# FC.net
KiCad netlist of a schematic drawn in Altium Designer
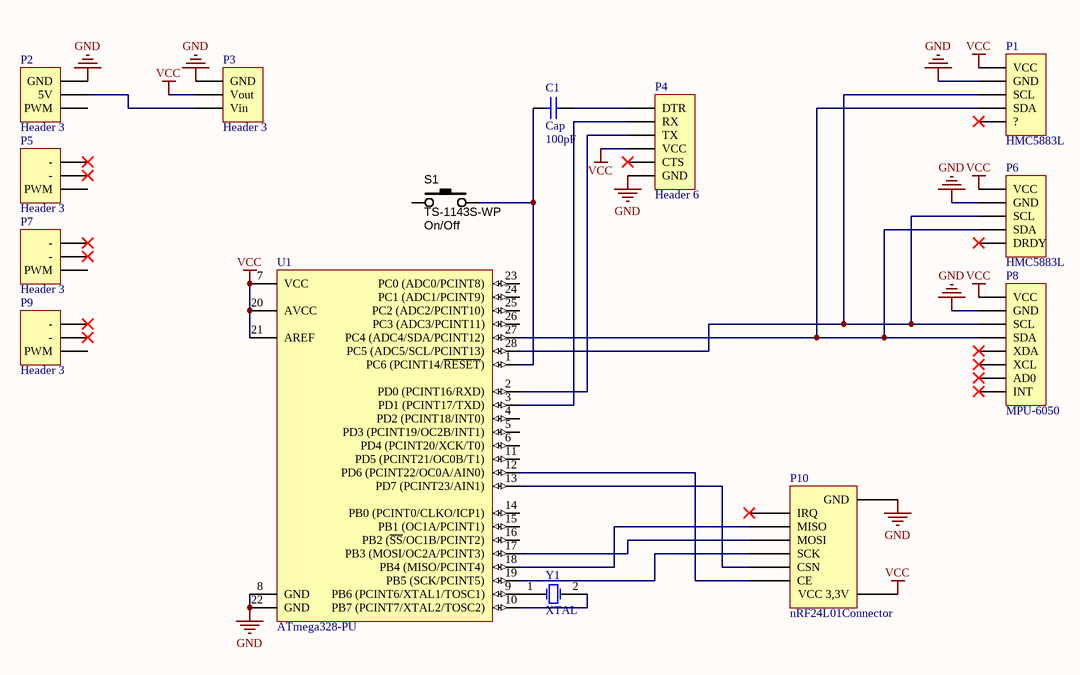
[diagram p0: FC.SchDoc]

(export (version "E")
  (design (tool "Eeschema 10.0.6"))
  (components
    (comp (ref "C1")
      (value "Cap")
      (footprint "RAD-0.3")
      (description "Capacitor")
      (fields (field (name "ALTIUM_VALUE") "100pF") (field (name "PUBLISHER") "Altium Limited"))
      (libsource (lib "Miscellaneous Devices") (part "Cap"))
    )
    (comp (ref "P1")
      (value "HMC5883L")
      (footprint "HDR1X5")
      (description "Header, 5-Pin")
      (fields (field (name "PUBLISHER") "Altium Limited"))
      (libsource (lib "Miscellaneous Connectors") (part "Header 5"))
    )
    (comp (ref "P2")
      (value "Header 3")
      (footprint "HDR1X3")
      (description "Header, 3-Pin")
      (fields (field (name "PUBLISHER") "Altium Limited"))
      (libsource (lib "Miscellaneous Connectors") (part "Header 3"))
    )
    (comp (ref "P3")
      (value "Header 3")
      (footprint "HDR1X3")
      (description "Header, 3-Pin")
      (fields (field (name "PUBLISHER") "Altium Limited"))
      (libsource (lib "") (part "Header 3_1"))
    )
    (comp (ref "P4")
      (value "Header 6")
      (footprint "HDR1X6")
      (description "Header, 6-Pin")
      (fields (field (name "PUBLISHER") "Altium Limited"))
      (libsource (lib "Miscellaneous Connectors") (part "Header 6"))
    )
    (comp (ref "P5")
      (value "Header 3")
      (footprint "HDR1X3")
      (description "Header, 3-Pin")
      (fields (field (name "PUBLISHER") "Altium Limited"))
      (libsource (lib "Miscellaneous Connectors") (part "Header 3"))
    )
    (comp (ref "P6")
      (value "HMC5883L")
      (footprint "HDR1X5")
      (description "Header, 5-Pin")
      (fields (field (name "PUBLISHER") "Altium Limited"))
      (libsource (lib "Miscellaneous Connectors") (part "Header 5"))
    )
    (comp (ref "P7")
      (value "Header 3")
      (footprint "HDR1X3")
      (description "Header, 3-Pin")
      (fields (field (name "PUBLISHER") "Altium Limited"))
      (libsource (lib "Miscellaneous Connectors") (part "Header 3"))
    )
    (comp (ref "P8")
      (value "MPU-6050")
      (footprint "HDR1X8")
      (description "Header, 8-Pin")
      (fields (field (name "PUBLISHER") "Altium Limited"))
      (libsource (lib "Miscellaneous Connectors") (part "Header 8"))
    )
    (comp (ref "P9")
      (value "Header 3")
      (footprint "HDR1X3")
      (description "Header, 3-Pin")
      (fields (field (name "PUBLISHER") "Altium Limited"))
      (libsource (lib "Miscellaneous Connectors") (part "Header 3"))
    )
    (comp (ref "P10")
      (value "nRF24L01Connector")
      (footprint "HDR2X4")
      (libsource (lib "nRF24L01Connector") (part "nRF24L01Connector"))
    )
    (comp (ref "S1")
      (value "TS-1143S-WP")
      (footprint "TS-1143S")
      (description "Switch SMD Tact 4.3mm Stem")
      (fields (field (name "FUNCTION") "On/Off"))
      (libsource (lib "PBL - Switches") (part "SW_SMD_PB_4.3mm"))
    )
    (comp (ref "U1")
      (value "ATmega328-PU")
      (footprint "28P3")
      (fields (field (name "PUBLISHER") "Altium Limited"))
      (libsource (lib "Atmel Microcontroller 8-Bit megaAVR") (part "ATmega328-PU"))
    )
    (comp (ref "Y1")
      (value "XTAL")
      (footprint "R38")
      (description "Crystal Oscillator")
      (fields (field (name "PUBLISHER") "Altium Limited"))
      (libsource (lib "Miscellaneous Devices") (part "XTAL"))
    )
  )
  (nets
    (net (code "1") (name "GND") (class "Default")
      (node (ref "P1") (pin "2") (pinfunction "GND_2") (pintype "passive"))
      (node (ref "P10") (pin "2") (pinfunction "GND_2") (pintype "passive"))
      (node (ref "P2") (pin "3") (pinfunction "-_3") (pintype "passive"))
      (node (ref "P3") (pin "1") (pinfunction "GND_1") (pintype "passive"))
      (node (ref "P4") (pin "6") (pinfunction "GND_6") (pintype "passive"))
      (node (ref "P6") (pin "2") (pinfunction "GND_2") (pintype "passive"))
      (node (ref "P8") (pin "2") (pinfunction "GND_2") (pintype "passive"))
      (node (ref "U1") (pin "22") (pinfunction "GND_22") (pintype "power_in"))
      (node (ref "U1") (pin "8") (pinfunction "GND_8") (pintype "power_in"))
    )
    (net (code "2") (name "Net-(P1-SCL)") (class "Default")
      (node (ref "P1") (pin "3") (pinfunction "SCL_3") (pintype "passive"))
      (node (ref "P6") (pin "3") (pinfunction "SCL_3") (pintype "passive"))
      (node (ref "P8") (pin "3") (pinfunction "SCL_3") (pintype "passive"))
      (node (ref "U1") (pin "28") (pinfunction "PC5_(ADC5/SCL/PCINT13)_28") (pintype "bidirectional"))
    )
    (net (code "3") (name "Net-(P1-SDA)") (class "Default")
      (node (ref "P1") (pin "4") (pinfunction "SDA_4") (pintype "passive"))
      (node (ref "P6") (pin "4") (pinfunction "SDA_4") (pintype "passive"))
      (node (ref "P8") (pin "4") (pinfunction "SDA_4") (pintype "passive"))
      (node (ref "U1") (pin "27") (pinfunction "PC4_(ADC4/SDA/PCINT12)_27") (pintype "bidirectional"))
    )
    (net (code "4") (name "Net-(P3-Vin)") (class "Default")
      (node (ref "P2") (pin "2") (pinfunction "-_2") (pintype "passive"))
      (node (ref "P3") (pin "3") (pinfunction "Vin_3") (pintype "passive"))
    )
    (net (code "5") (name "Net-(P4-DTR)") (class "Default")
      (node (ref "C1") (pin "2") (pinfunction "2_2") (pintype "passive"))
      (node (ref "P4") (pin "1") (pinfunction "DTR_1") (pintype "passive"))
    )
    (net (code "6") (name "Net-(P4-RX)") (class "Default")
      (node (ref "P4") (pin "2") (pinfunction "RX_2") (pintype "passive"))
      (node (ref "U1") (pin "3") (pinfunction "PD1_(PCINT17/TXD)_3") (pintype "bidirectional"))
    )
    (net (code "7") (name "Net-(P4-TX)") (class "Default")
      (node (ref "P4") (pin "3") (pinfunction "TX_3") (pintype "passive"))
      (node (ref "U1") (pin "2") (pinfunction "PD0_(PCINT16/RXD)_2") (pintype "bidirectional"))
    )
    (net (code "8") (name "Net-(P10-CE)") (class "Default")
      (node (ref "P10") (pin "3") (pinfunction "CE_3") (pintype "passive"))
      (node (ref "U1") (pin "12") (pinfunction "PD6_(PCINT22/OC0A/AIN0)_12") (pintype "bidirectional"))
    )
    (net (code "9") (name "Net-(P10-CSN)") (class "Default")
      (node (ref "P10") (pin "4") (pinfunction "CSN_4") (pintype "passive"))
      (node (ref "U1") (pin "13") (pinfunction "PD7_(PCINT23/AIN1)_13") (pintype "bidirectional"))
    )
    (net (code "10") (name "Net-(P10-MISO)") (class "Default")
      (node (ref "P10") (pin "7") (pinfunction "MISO_7") (pintype "passive"))
      (node (ref "U1") (pin "18") (pinfunction "PB4_(MISO/PCINT4)_18") (pintype "bidirectional"))
    )
    (net (code "11") (name "Net-(P10-MOSI)") (class "Default")
      (node (ref "P10") (pin "6") (pinfunction "MOSI_6") (pintype "passive"))
      (node (ref "U1") (pin "17") (pinfunction "PB3_(MOSI/OC2A/PCINT3)_17") (pintype "bidirectional"))
    )
    (net (code "12") (name "Net-(P10-SCK)") (class "Default")
      (node (ref "P10") (pin "5") (pinfunction "SCK_5") (pintype "passive"))
      (node (ref "U1") (pin "19") (pinfunction "PB5_(SCK/PCINT5)_19") (pintype "bidirectional"))
    )
    (net (code "13") (name "Net-(U1-PB6_(PCINT6{slash}XTAL1{slash}TOSC1))") (class "Default")
      (node (ref "U1") (pin "9") (pinfunction "PB6_(PCINT6/XTAL1/TOSC1)_9") (pintype "bidirectional"))
      (node (ref "Y1") (pin "1") (pinfunction "OSC1_1") (pintype "passive"))
    )
    (net (code "14") (name "Net-(U1-PB7_(PCINT7{slash}XTAL2{slash}TOSC2))") (class "Default")
      (node (ref "U1") (pin "10") (pinfunction "PB7_(PCINT7/XTAL2/TOSC2)_10") (pintype "bidirectional"))
      (node (ref "Y1") (pin "2") (pinfunction "OSC2_2") (pintype "passive"))
    )
    (net (code "15") (name "Net-(U1-PC6_(PCINT14{slash}~{RESET}))") (class "Default")
      (node (ref "C1") (pin "1") (pinfunction "1_1") (pintype "passive"))
      (node (ref "S1") (pin "2") (pintype "passive"))
      (node (ref "U1") (pin "1") (pinfunction "PC6_(PCINT14/~{RESET})_1") (pintype "bidirectional"))
    )
    (net (code "16") (name "VCC") (class "Default")
      (node (ref "P1") (pin "1") (pinfunction "VCC_1") (pintype "passive"))
      (node (ref "P10") (pin "1") (pinfunction "VCC_3,3V_1") (pintype "passive"))
      (node (ref "P3") (pin "2") (pinfunction "Vout_2") (pintype "passive"))
      (node (ref "P4") (pin "4") (pinfunction "VCC_4") (pintype "passive"))
      (node (ref "P6") (pin "1") (pinfunction "VCC_1") (pintype "passive"))
      (node (ref "P8") (pin "1") (pinfunction "VCC_1") (pintype "passive"))
      (node (ref "U1") (pin "20") (pinfunction "AVCC_20") (pintype "power_in"))
      (node (ref "U1") (pin "21") (pinfunction "AREF_21") (pintype "power_in"))
      (node (ref "U1") (pin "7") (pinfunction "VCC_7") (pintype "power_in"))
    )
    (net (code "17") (name "unconnected-(P1-DRDY-Pad5)") (class "Default")
      (node (ref "P1") (pin "5") (pinfunction "DRDY_5") (pintype "passive+no_connect"))
    )
    (net (code "18") (name "unconnected-(P2-PWM-Pad1)") (class "Default")
      (node (ref "P2") (pin "1") (pinfunction "PWM_1") (pintype "passive"))
    )
    (net (code "19") (name "unconnected-(P4-CTS-Pad5)") (class "Default")
      (node (ref "P4") (pin "5") (pinfunction "CTS_5") (pintype "passive+no_connect"))
    )
    (net (code "20") (name "unconnected-(P5---Pad2)") (class "Default")
      (node (ref "P5") (pin "2") (pinfunction "-_2") (pintype "passive+no_connect"))
    )
    (net (code "21") (name "unconnected-(P5---Pad3)") (class "Default")
      (node (ref "P5") (pin "3") (pinfunction "-_3") (pintype "passive+no_connect"))
    )
    (net (code "22") (name "unconnected-(P5-PWM-Pad1)") (class "Default")
      (node (ref "P5") (pin "1") (pinfunction "PWM_1") (pintype "passive"))
    )
    (net (code "23") (name "unconnected-(P6-DRDY-Pad5)") (class "Default")
      (node (ref "P6") (pin "5") (pinfunction "DRDY_5") (pintype "passive+no_connect"))
    )
    (net (code "24") (name "unconnected-(P7---Pad2)") (class "Default")
      (node (ref "P7") (pin "2") (pinfunction "-_2") (pintype "passive+no_connect"))
    )
    (net (code "25") (name "unconnected-(P7---Pad3)") (class "Default")
      (node (ref "P7") (pin "3") (pinfunction "-_3") (pintype "passive+no_connect"))
    )
    (net (code "26") (name "unconnected-(P7-PWM-Pad1)") (class "Default")
      (node (ref "P7") (pin "1") (pinfunction "PWM_1") (pintype "passive"))
    )
    (net (code "27") (name "unconnected-(P8-AD0-Pad7)") (class "Default")
      (node (ref "P8") (pin "7") (pinfunction "AD0_7") (pintype "passive+no_connect"))
    )
    (net (code "28") (name "unconnected-(P8-INT-Pad8)") (class "Default")
      (node (ref "P8") (pin "8") (pinfunction "INT_8") (pintype "passive+no_connect"))
    )
    (net (code "29") (name "unconnected-(P8-XCL-Pad6)") (class "Default")
      (node (ref "P8") (pin "6") (pinfunction "XCL_6") (pintype "passive+no_connect"))
    )
    (net (code "30") (name "unconnected-(P8-XDA-Pad5)") (class "Default")
      (node (ref "P8") (pin "5") (pinfunction "XDA_5") (pintype "passive+no_connect"))
    )
    (net (code "31") (name "unconnected-(P9---Pad2)") (class "Default")
      (node (ref "P9") (pin "2") (pinfunction "-_2") (pintype "passive+no_connect"))
    )
    (net (code "32") (name "unconnected-(P9---Pad3)") (class "Default")
      (node (ref "P9") (pin "3") (pinfunction "-_3") (pintype "passive+no_connect"))
    )
    (net (code "33") (name "unconnected-(P9-PWM-Pad1)") (class "Default")
      (node (ref "P9") (pin "1") (pinfunction "PWM_1") (pintype "passive"))
    )
    (net (code "34") (name "unconnected-(P10-IRQ-Pad8)") (class "Default")
      (node (ref "P10") (pin "8") (pinfunction "IRQ_8") (pintype "passive+no_connect"))
    )
    (net (code "35") (name "unconnected-(S1-Pad1)") (class "Default")
      (node (ref "S1") (pin "1") (pintype "passive"))
    )
    (net (code "36") (name "unconnected-(U1-PB0_(PCINT0{slash}CLKO{slash}ICP1)-Pad14)") (class "Default")
      (node (ref "U1") (pin "14") (pinfunction "PB0_(PCINT0/CLKO/ICP1)_14") (pintype "bidirectional"))
    )
    (net (code "37") (name "unconnected-(U1-PB1_(OC1A{slash}PCINT1)-Pad15)") (class "Default")
      (node (ref "U1") (pin "15") (pinfunction "PB1_(OC1A/PCINT1)_15") (pintype "bidirectional"))
    )
    (net (code "38") (name "unconnected-(U1-PB2_(~{SS}{slash}OC1B{slash}PCINT2)-Pad16)") (class "Default")
      (node (ref "U1") (pin "16") (pinfunction "PB2_(~{SS}/OC1B/PCINT2)_16") (pintype "bidirectional"))
    )
    (net (code "39") (name "unconnected-(U1-PC0_(ADC0{slash}PCINT8)-Pad23)") (class "Default")
      (node (ref "U1") (pin "23") (pinfunction "PC0_(ADC0/PCINT8)_23") (pintype "bidirectional"))
    )
    (net (code "40") (name "unconnected-(U1-PC1_(ADC1{slash}PCINT9)-Pad24)") (class "Default")
      (node (ref "U1") (pin "24") (pinfunction "PC1_(ADC1/PCINT9)_24") (pintype "bidirectional"))
    )
    (net (code "41") (name "unconnected-(U1-PC2_(ADC2{slash}PCINT10)-Pad25)") (class "Default")
      (node (ref "U1") (pin "25") (pinfunction "PC2_(ADC2/PCINT10)_25") (pintype "bidirectional"))
    )
    (net (code "42") (name "unconnected-(U1-PC3_(ADC3{slash}PCINT11)-Pad26)") (class "Default")
      (node (ref "U1") (pin "26") (pinfunction "PC3_(ADC3/PCINT11)_26") (pintype "bidirectional"))
    )
    (net (code "43") (name "unconnected-(U1-PD2_(PCINT18{slash}INT0)-Pad4)") (class "Default")
      (node (ref "U1") (pin "4") (pinfunction "PD2_(PCINT18/INT0)_4") (pintype "bidirectional"))
    )
    (net (code "44") (name "unconnected-(U1-PD3_(PCINT19{slash}OC2B{slash}INT1)-Pad5)") (class "Default")
      (node (ref "U1") (pin "5") (pinfunction "PD3_(PCINT19/OC2B/INT1)_5") (pintype "bidirectional"))
    )
    (net (code "45") (name "unconnected-(U1-PD4_(PCINT20{slash}XCK{slash}T0)-Pad6)") (class "Default")
      (node (ref "U1") (pin "6") (pinfunction "PD4_(PCINT20/XCK/T0)_6") (pintype "bidirectional"))
    )
    (net (code "46") (name "unconnected-(U1-PD5_(PCINT21{slash}OC0B{slash}T1)-Pad11)") (class "Default")
      (node (ref "U1") (pin "11") (pinfunction "PD5_(PCINT21/OC0B/T1)_11") (pintype "bidirectional"))
    )
  )
)
